# RS485.net
KiCad netlist of a schematic drawn in Altium Designer
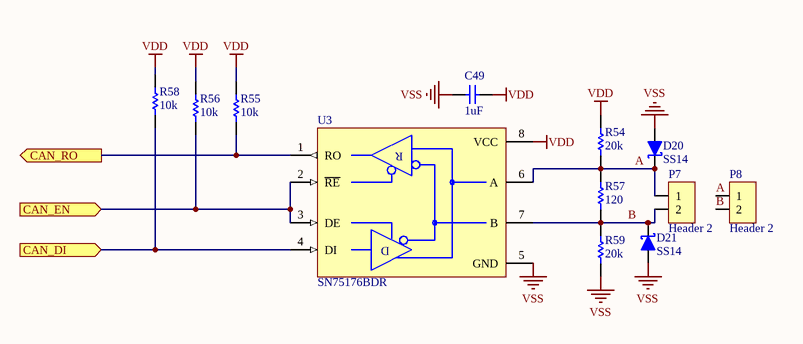
[diagram p0: RS485.SchDoc]

(export (version "E")
  (design (tool "Eeschema 10.0.6"))
  (components
    (comp (ref "C49")
      (value "1uF")
      (footprint "C 0805")
      (description "Capacitor non-pol")
      (libsource (lib "BKIT4U_LIB") (part "Capacitor NP"))
    )
    (comp (ref "D20")
      (value "SS14")
      (footprint "DO-214AC (SMA)")
      (description "Schottky Diode")
      (fields (field (name "PUBLISHER") "Altium Limited"))
      (libsource (lib "BKIT4U_LIB") (part "Diode Schottky"))
    )
    (comp (ref "D21")
      (value "SS14")
      (footprint "DO-214AC (SMA)")
      (description "Schottky Diode")
      (fields (field (name "PUBLISHER") "Altium Limited"))
      (libsource (lib "BKIT4U_LIB") (part "Diode Schottky"))
    )
    (comp (ref "P7")
      (value "Header 2")
      (footprint "HDR/Terminal/2/5mm/RA")
      (description "Header, 2-Pin")
      (fields (field (name "PUBLISHER") "Altium Limited"))
      (libsource (lib "BKIT4U_LIB") (part "Header 2"))
    )
    (comp (ref "P8")
      (value "Header 2")
      (footprint "HDR/Terminal/2/5mm/RA")
      (description "Header, 2-Pin")
      (fields (field (name "PUBLISHER") "Altium Limited"))
      (libsource (lib "BKIT4U_LIB") (part "Header 2"))
    )
    (comp (ref "R54")
      (value "20k")
      (footprint "R 0805")
      (description "Resistor")
      (fields (field (name "PUBLISHER") "Altium Limited"))
      (libsource (lib "BKIT4U_LIB") (part "Resistor"))
    )
    (comp (ref "R55")
      (value "10k")
      (footprint "R 0805")
      (description "Resistor")
      (fields (field (name "PUBLISHER") "Altium Limited"))
      (libsource (lib "BKIT4U_LIB") (part "Resistor"))
    )
    (comp (ref "R56")
      (value "10k")
      (footprint "R 0805")
      (description "Resistor")
      (fields (field (name "PUBLISHER") "Altium Limited"))
      (libsource (lib "BKIT4U_LIB") (part "Resistor"))
    )
    (comp (ref "R57")
      (value "120")
      (footprint "R 0805")
      (description "Resistor")
      (fields (field (name "PUBLISHER") "Altium Limited"))
      (libsource (lib "BKIT4U_LIB") (part "Resistor"))
    )
    (comp (ref "R58")
      (value "10k")
      (footprint "R 0805")
      (description "Resistor")
      (fields (field (name "PUBLISHER") "Altium Limited"))
      (libsource (lib "BKIT4U_LIB") (part "Resistor"))
    )
    (comp (ref "R59")
      (value "20k")
      (footprint "R 0805")
      (description "Resistor")
      (fields (field (name "PUBLISHER") "Altium Limited"))
      (libsource (lib "BKIT4U_LIB") (part "Resistor"))
    )
    (comp (ref "U3") (value "SN75176BDR") (footprint "SOIC-8") (libsource (lib "BKIT4U_LIB") (part "MAX485")))
  )
  (nets
    (net (code "1") (name "/A") (class "Default")
      (node (ref "D20") (pin "2") (pinfunction "K_2") (pintype "passive"))
      (node (ref "P7") (pin "1") (pinfunction "1_1") (pintype "passive"))
      (node (ref "P8") (pin "1") (pinfunction "1_1") (pintype "passive"))
      (node (ref "R54") (pin "1") (pinfunction "1_1") (pintype "passive"))
      (node (ref "R57") (pin "2") (pinfunction "2_2") (pintype "passive"))
      (node (ref "U3") (pin "6") (pinfunction "A_6") (pintype "passive"))
    )
    (net (code "2") (name "/B") (class "Default")
      (node (ref "D21") (pin "2") (pinfunction "K_2") (pintype "passive"))
      (node (ref "P7") (pin "2") (pinfunction "2_2") (pintype "passive"))
      (node (ref "P8") (pin "2") (pinfunction "2_2") (pintype "passive"))
      (node (ref "R57") (pin "1") (pinfunction "1_1") (pintype "passive"))
      (node (ref "R59") (pin "2") (pinfunction "2_2") (pintype "passive"))
      (node (ref "U3") (pin "7") (pinfunction "B_7") (pintype "passive"))
    )
    (net (code "3") (name "/CAN_DI") (class "Default")
      (node (ref "R58") (pin "1") (pinfunction "1_1") (pintype "passive"))
      (node (ref "U3") (pin "4") (pinfunction "DI_4") (pintype "input"))
    )
    (net (code "4") (name "/CAN_EN") (class "Default")
      (node (ref "R56") (pin "1") (pinfunction "1_1") (pintype "passive"))
      (node (ref "U3") (pin "2") (pinfunction "~{RE}_2") (pintype "input"))
      (node (ref "U3") (pin "3") (pinfunction "DE_3") (pintype "input"))
    )
    (net (code "5") (name "/CAN_RO") (class "Default")
      (node (ref "R55") (pin "2") (pinfunction "2_2") (pintype "passive"))
      (node (ref "U3") (pin "1") (pinfunction "RO_1") (pintype "output"))
    )
    (net (code "6") (name "VDD") (class "Default")
      (node (ref "C49") (pin "1") (pinfunction "1_1") (pintype "passive"))
      (node (ref "R54") (pin "2") (pinfunction "2_2") (pintype "passive"))
      (node (ref "R55") (pin "1") (pinfunction "1_1") (pintype "passive"))
      (node (ref "R56") (pin "2") (pinfunction "2_2") (pintype "passive"))
      (node (ref "R58") (pin "2") (pinfunction "2_2") (pintype "passive"))
      (node (ref "U3") (pin "8") (pinfunction "VCC_8") (pintype "passive"))
    )
    (net (code "7") (name "VSS") (class "Default")
      (node (ref "C49") (pin "2") (pinfunction "2_2") (pintype "passive"))
      (node (ref "D20") (pin "1") (pinfunction "A_1") (pintype "passive"))
      (node (ref "D21") (pin "1") (pinfunction "A_1") (pintype "passive"))
      (node (ref "R59") (pin "1") (pinfunction "1_1") (pintype "passive"))
      (node (ref "U3") (pin "5") (pinfunction "GND_5") (pintype "power_in"))
    )
  )
)
